# SCH_ESP32-Gate-Module_2024-04-16.net
KiCad netlist of a schematic drawn in EasyEDA
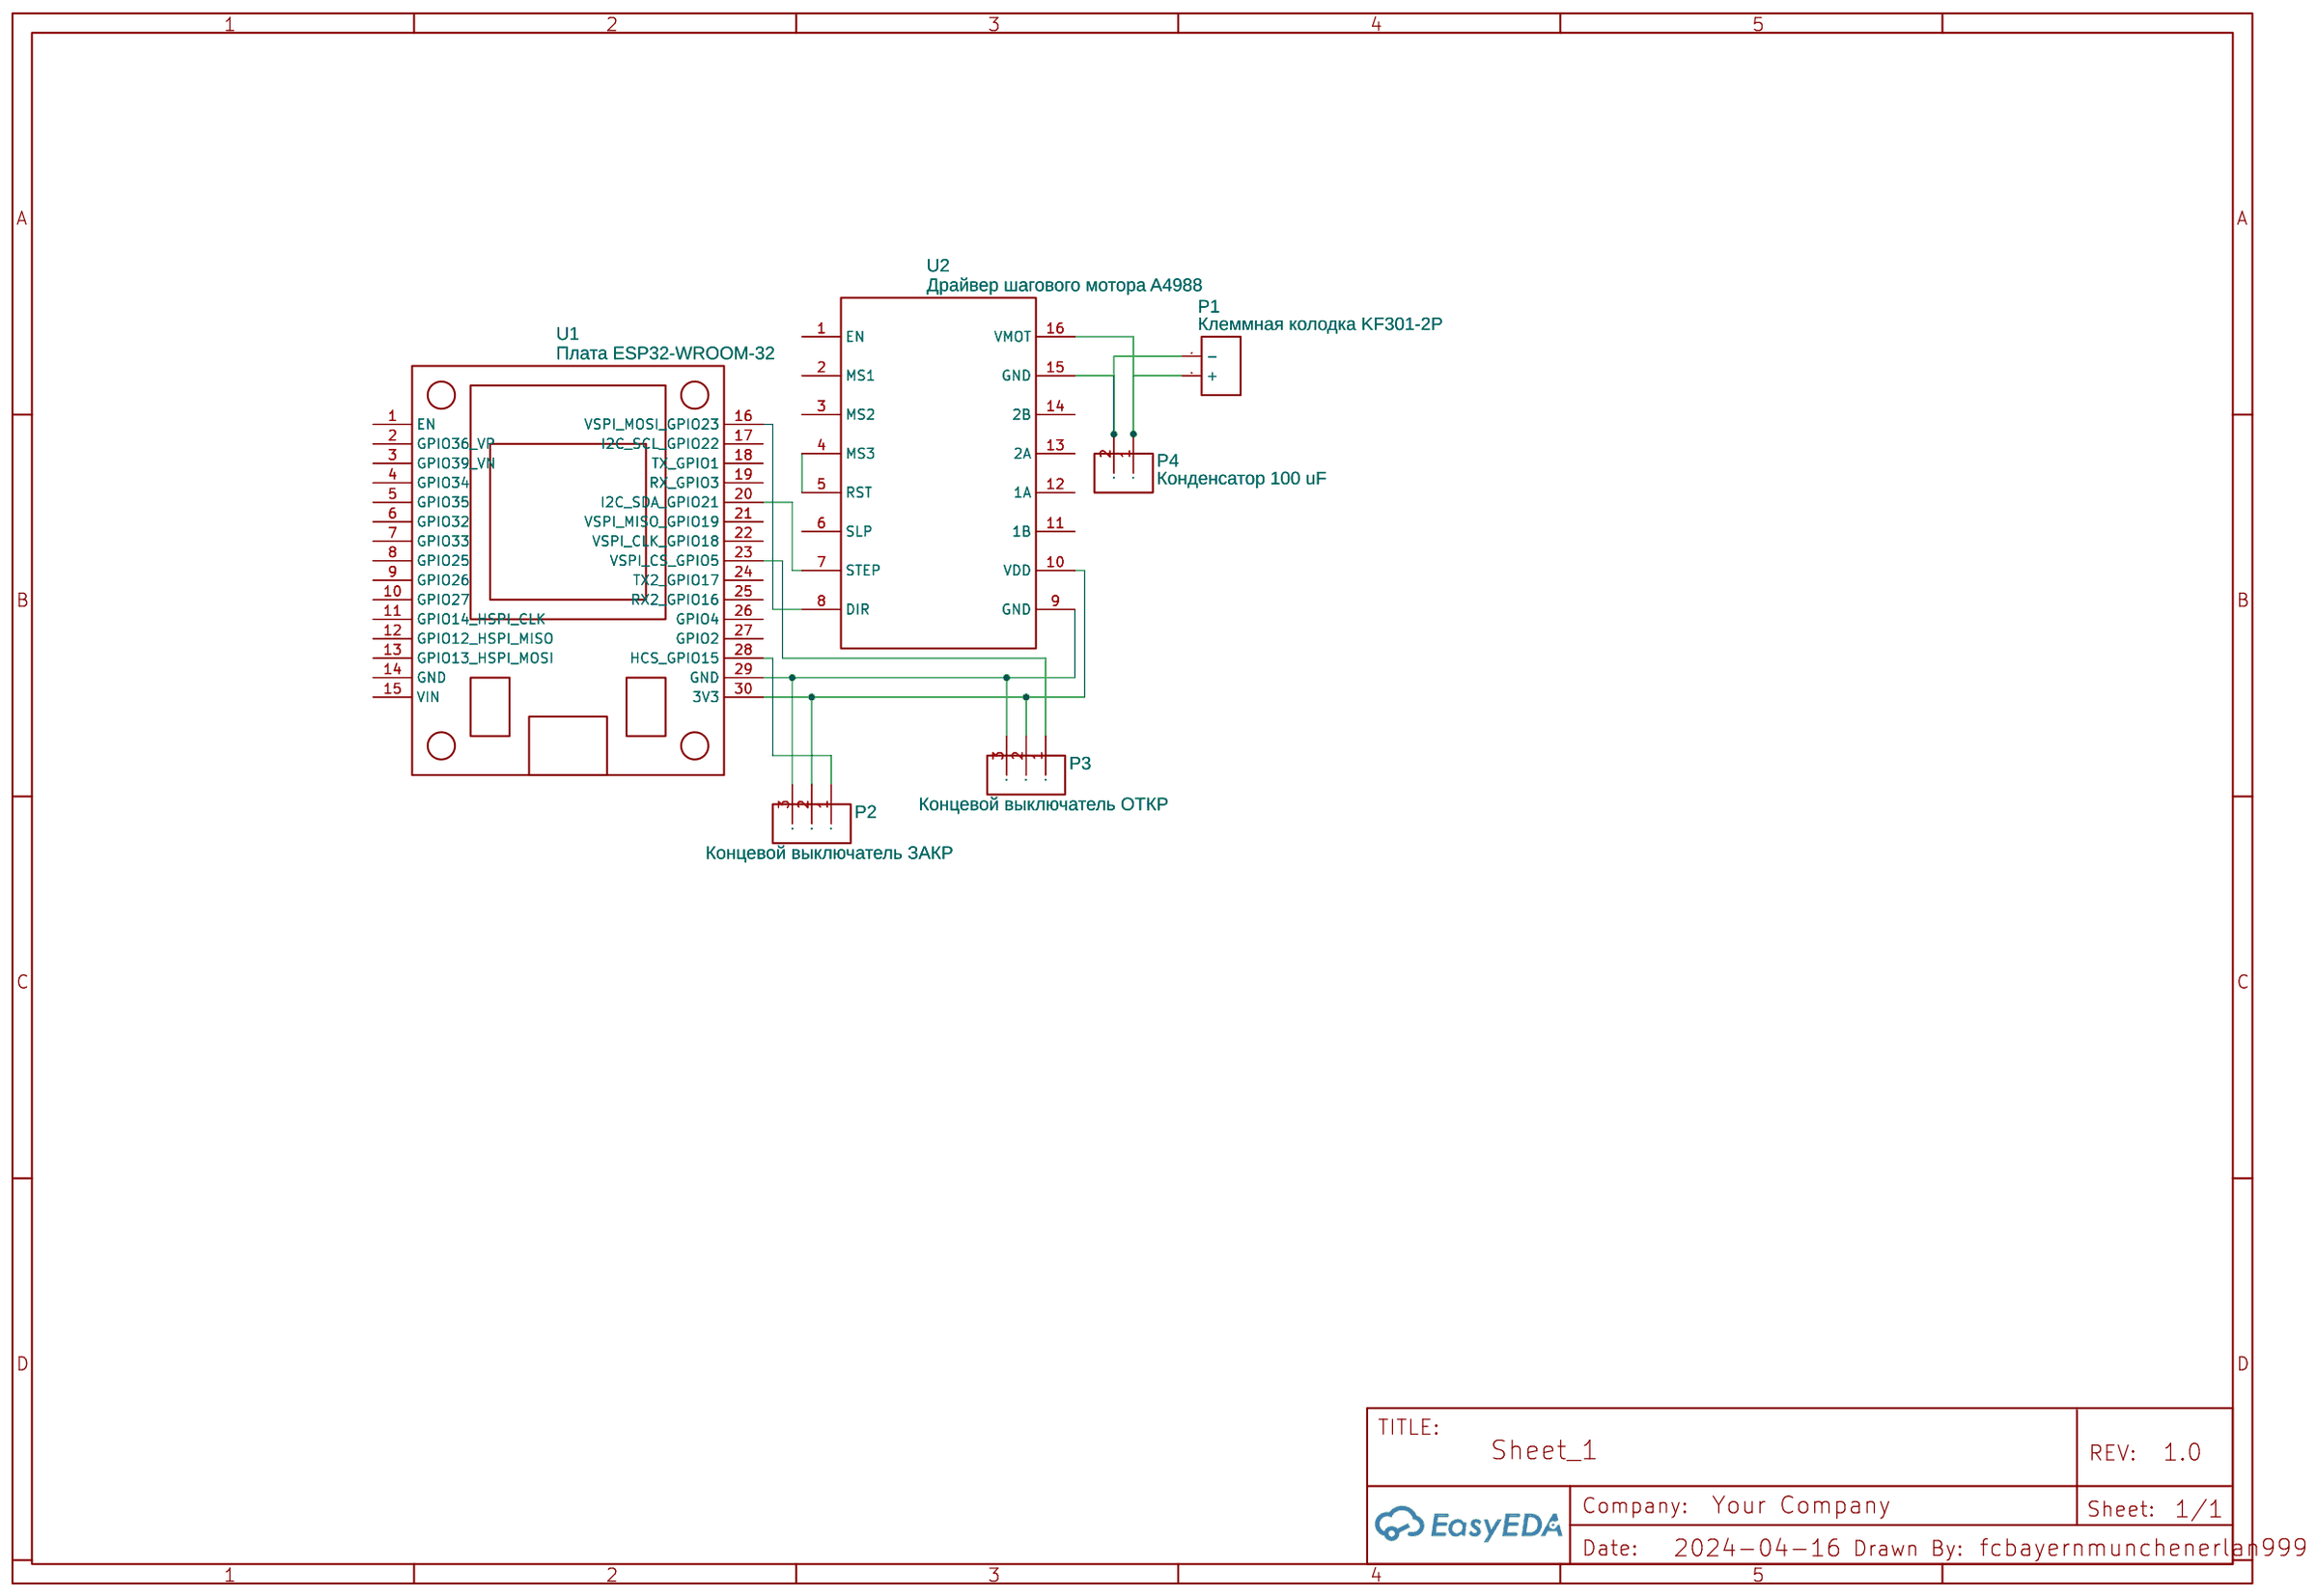
[diagram p0: schematic sheet]

(export (version "E")
  (design (tool "Eeschema 10.0.6"))
  (components
    (comp (ref "P1") (value "Клеммная колодка KF301-2P") (libsource (lib "") (part "CONN-TH_2P-P5.00")))
    (comp (ref "P2") (value "Концевой выключатель ЗАКР") (libsource (lib "") (part "3x2.54 XHP-3 JST case")))
    (comp (ref "P3") (value "Концевой выключатель ОТКР") (libsource (lib "") (part "3x2.54 XHP-3 JST case")))
    (comp (ref "P4") (value "Конденсатор 100 uF") (libsource (lib "") (part "2x2.54 XHP-2 JST case")))
    (comp (ref "U1") (value "Плата ESP32-WROOM-32") (libsource (lib "") (part "Плата ESP32 (вариант 2)")))
    (comp (ref "U2")
      (value "Драйвер шагового мотора A4988")
      (libsource (lib "") (part "A4988 Stepper Motor Driver Carrier"))
    )
  )
  (nets
    (net (code "1") (name "Net-(P1-+)") (class "Default")
      (node (ref "P1") (pin "2") (pinfunction "+_2") (pintype "unspecified"))
      (node (ref "P4") (pin "1") (pinfunction "1_1") (pintype "unspecified"))
      (node (ref "U2") (pin "16") (pinfunction "VMOT_16") (pintype "unspecified"))
    )
    (net (code "2") (name "Net-(P1--)") (class "Default")
      (node (ref "P1") (pin "1") (pinfunction "-_1") (pintype "unspecified"))
      (node (ref "P4") (pin "2") (pinfunction "2_2") (pintype "unspecified"))
      (node (ref "U2") (pin "15") (pinfunction "GND_15") (pintype "unspecified"))
    )
    (net (code "3") (name "Net-(P2-Pad3)") (class "Default")
      (node (ref "P2") (pin "3") (pinfunction "3_3") (pintype "unspecified"))
      (node (ref "P3") (pin "3") (pinfunction "3_3") (pintype "unspecified"))
      (node (ref "U1") (pin "29") (pinfunction "GND_29") (pintype "bidirectional"))
      (node (ref "U2") (pin "9") (pinfunction "GND_9") (pintype "unspecified"))
    )
    (net (code "4") (name "Net-(U1-3V3)") (class "Default")
      (node (ref "P2") (pin "2") (pinfunction "2_2") (pintype "unspecified"))
      (node (ref "P3") (pin "2") (pinfunction "2_2") (pintype "unspecified"))
      (node (ref "U1") (pin "30") (pinfunction "3V3_30") (pintype "bidirectional"))
      (node (ref "U2") (pin "10") (pinfunction "VDD_10") (pintype "unspecified"))
    )
    (net (code "5") (name "Net-(U1-HCS_GPIO15)") (class "Default")
      (node (ref "P2") (pin "1") (pinfunction "1_1") (pintype "unspecified"))
      (node (ref "U1") (pin "28") (pinfunction "HCS_GPIO15_28") (pintype "bidirectional"))
    )
    (net (code "6") (name "Net-(U1-I2C_SDA_GPIO21)") (class "Default")
      (node (ref "U1") (pin "20") (pinfunction "I2C_SDA_GPIO21_20") (pintype "bidirectional"))
      (node (ref "U2") (pin "7") (pinfunction "STEP_7") (pintype "unspecified"))
    )
    (net (code "7") (name "Net-(U1-VSPI_CS_GPIO5)") (class "Default")
      (node (ref "P3") (pin "1") (pinfunction "1_1") (pintype "unspecified"))
      (node (ref "U1") (pin "23") (pinfunction "VSPI_CS_GPIO5_23") (pintype "bidirectional"))
    )
    (net (code "8") (name "Net-(U1-VSPI_MOSI_GPIO23)") (class "Default")
      (node (ref "U1") (pin "16") (pinfunction "VSPI_MOSI_GPIO23_16") (pintype "passive"))
      (node (ref "U2") (pin "8") (pinfunction "DIR_8") (pintype "unspecified"))
    )
    (net (code "9") (name "Net-(U2-MS3)") (class "Default")
      (node (ref "U2") (pin "4") (pinfunction "MS3_4") (pintype "unspecified"))
      (node (ref "U2") (pin "5") (pinfunction "RST_5") (pintype "unspecified"))
    )
    (net (code "10") (name "unconnected-(U1-EN-Pad1)") (class "Default")
      (node (ref "U1") (pin "1") (pinfunction "EN_1") (pintype "passive"))
    )
    (net (code "11") (name "unconnected-(U1-GND-Pad14)") (class "Default")
      (node (ref "U1") (pin "14") (pinfunction "GND_14") (pintype "passive"))
    )
    (net (code "12") (name "unconnected-(U1-GPIO2-Pad27)") (class "Default")
      (node (ref "U1") (pin "27") (pinfunction "GPIO2_27") (pintype "bidirectional"))
    )
    (net (code "13") (name "unconnected-(U1-GPIO4-Pad26)") (class "Default")
      (node (ref "U1") (pin "26") (pinfunction "GPIO4_26") (pintype "bidirectional"))
    )
    (net (code "14") (name "unconnected-(U1-GPIO12_HSPI_MISO-Pad12)") (class "Default")
      (node (ref "U1") (pin "12") (pinfunction "GPIO12_HSPI_MISO_12") (pintype "bidirectional"))
    )
    (net (code "15") (name "unconnected-(U1-GPIO13_HSPI_MOSI-Pad13)") (class "Default")
      (node (ref "U1") (pin "13") (pinfunction "GPIO13_HSPI_MOSI_13") (pintype "bidirectional"))
    )
    (net (code "16") (name "unconnected-(U1-GPIO14_HSPI_CLK-Pad11)") (class "Default")
      (node (ref "U1") (pin "11") (pinfunction "GPIO14_HSPI_CLK_11") (pintype "bidirectional"))
    )
    (net (code "17") (name "unconnected-(U1-GPIO25-Pad8)") (class "Default")
      (node (ref "U1") (pin "8") (pinfunction "GPIO25_8") (pintype "bidirectional"))
    )
    (net (code "18") (name "unconnected-(U1-GPIO26-Pad9)") (class "Default")
      (node (ref "U1") (pin "9") (pinfunction "GPIO26_9") (pintype "bidirectional"))
    )
    (net (code "19") (name "unconnected-(U1-GPIO27-Pad10)") (class "Default")
      (node (ref "U1") (pin "10") (pinfunction "GPIO27_10") (pintype "bidirectional"))
    )
    (net (code "20") (name "unconnected-(U1-GPIO32-Pad6)") (class "Default")
      (node (ref "U1") (pin "6") (pinfunction "GPIO32_6") (pintype "bidirectional"))
    )
    (net (code "21") (name "unconnected-(U1-GPIO33-Pad7)") (class "Default")
      (node (ref "U1") (pin "7") (pinfunction "GPIO33_7") (pintype "bidirectional"))
    )
    (net (code "22") (name "unconnected-(U1-GPIO34-Pad4)") (class "Default")
      (node (ref "U1") (pin "4") (pinfunction "GPIO34_4") (pintype "bidirectional"))
    )
    (net (code "23") (name "unconnected-(U1-GPIO35-Pad5)") (class "Default")
      (node (ref "U1") (pin "5") (pinfunction "GPIO35_5") (pintype "bidirectional"))
    )
    (net (code "24") (name "unconnected-(U1-GPIO36_VP-Pad2)") (class "Default")
      (node (ref "U1") (pin "2") (pinfunction "GPIO36_VP_2") (pintype "bidirectional"))
    )
    (net (code "25") (name "unconnected-(U1-GPIO39_VN-Pad3)") (class "Default")
      (node (ref "U1") (pin "3") (pinfunction "GPIO39_VN_3") (pintype "bidirectional"))
    )
    (net (code "26") (name "unconnected-(U1-I2C_SCL_GPIO22-Pad17)") (class "Default")
      (node (ref "U1") (pin "17") (pinfunction "I2C_SCL_GPIO22_17") (pintype "bidirectional"))
    )
    (net (code "27") (name "unconnected-(U1-RX2_GPIO16-Pad25)") (class "Default")
      (node (ref "U1") (pin "25") (pinfunction "RX2_GPIO16_25") (pintype "bidirectional"))
    )
    (net (code "28") (name "unconnected-(U1-RX_GPIO3-Pad19)") (class "Default")
      (node (ref "U1") (pin "19") (pinfunction "RX_GPIO3_19") (pintype "bidirectional"))
    )
    (net (code "29") (name "unconnected-(U1-TX2_GPIO17-Pad24)") (class "Default")
      (node (ref "U1") (pin "24") (pinfunction "TX2_GPIO17_24") (pintype "bidirectional"))
    )
    (net (code "30") (name "unconnected-(U1-TX_GPIO1-Pad18)") (class "Default")
      (node (ref "U1") (pin "18") (pinfunction "TX_GPIO1_18") (pintype "bidirectional"))
    )
    (net (code "31") (name "unconnected-(U1-VIN-Pad15)") (class "Default")
      (node (ref "U1") (pin "15") (pinfunction "VIN_15") (pintype "bidirectional"))
    )
    (net (code "32") (name "unconnected-(U1-VSPI_CLK_GPIO18-Pad22)") (class "Default")
      (node (ref "U1") (pin "22") (pinfunction "VSPI_CLK_GPIO18_22") (pintype "passive"))
    )
    (net (code "33") (name "unconnected-(U1-VSPI_MISO_GPIO19-Pad21)") (class "Default")
      (node (ref "U1") (pin "21") (pinfunction "VSPI_MISO_GPIO19_21") (pintype "bidirectional"))
    )
    (net (code "34") (name "unconnected-(U2-1A-Pad12)") (class "Default")
      (node (ref "U2") (pin "12") (pinfunction "1A_12") (pintype "unspecified"))
    )
    (net (code "35") (name "unconnected-(U2-1B-Pad11)") (class "Default")
      (node (ref "U2") (pin "11") (pinfunction "1B_11") (pintype "unspecified"))
    )
    (net (code "36") (name "unconnected-(U2-2A-Pad13)") (class "Default")
      (node (ref "U2") (pin "13") (pinfunction "2A_13") (pintype "unspecified"))
    )
    (net (code "37") (name "unconnected-(U2-2B-Pad14)") (class "Default")
      (node (ref "U2") (pin "14") (pinfunction "2B_14") (pintype "unspecified"))
    )
    (net (code "38") (name "unconnected-(U2-EN-Pad1)") (class "Default")
      (node (ref "U2") (pin "1") (pinfunction "EN_1") (pintype "unspecified"))
    )
    (net (code "39") (name "unconnected-(U2-MS1-Pad2)") (class "Default")
      (node (ref "U2") (pin "2") (pinfunction "MS1_2") (pintype "unspecified"))
    )
    (net (code "40") (name "unconnected-(U2-MS2-Pad3)") (class "Default")
      (node (ref "U2") (pin "3") (pinfunction "MS2_3") (pintype "unspecified"))
    )
    (net (code "41") (name "unconnected-(U2-SLP-Pad6)") (class "Default")
      (node (ref "U2") (pin "6") (pinfunction "SLP_6") (pintype "unspecified"))
    )
  )
)
